# FiberLink_RS232.net
KiCad netlist of a schematic drawn in EAGLE
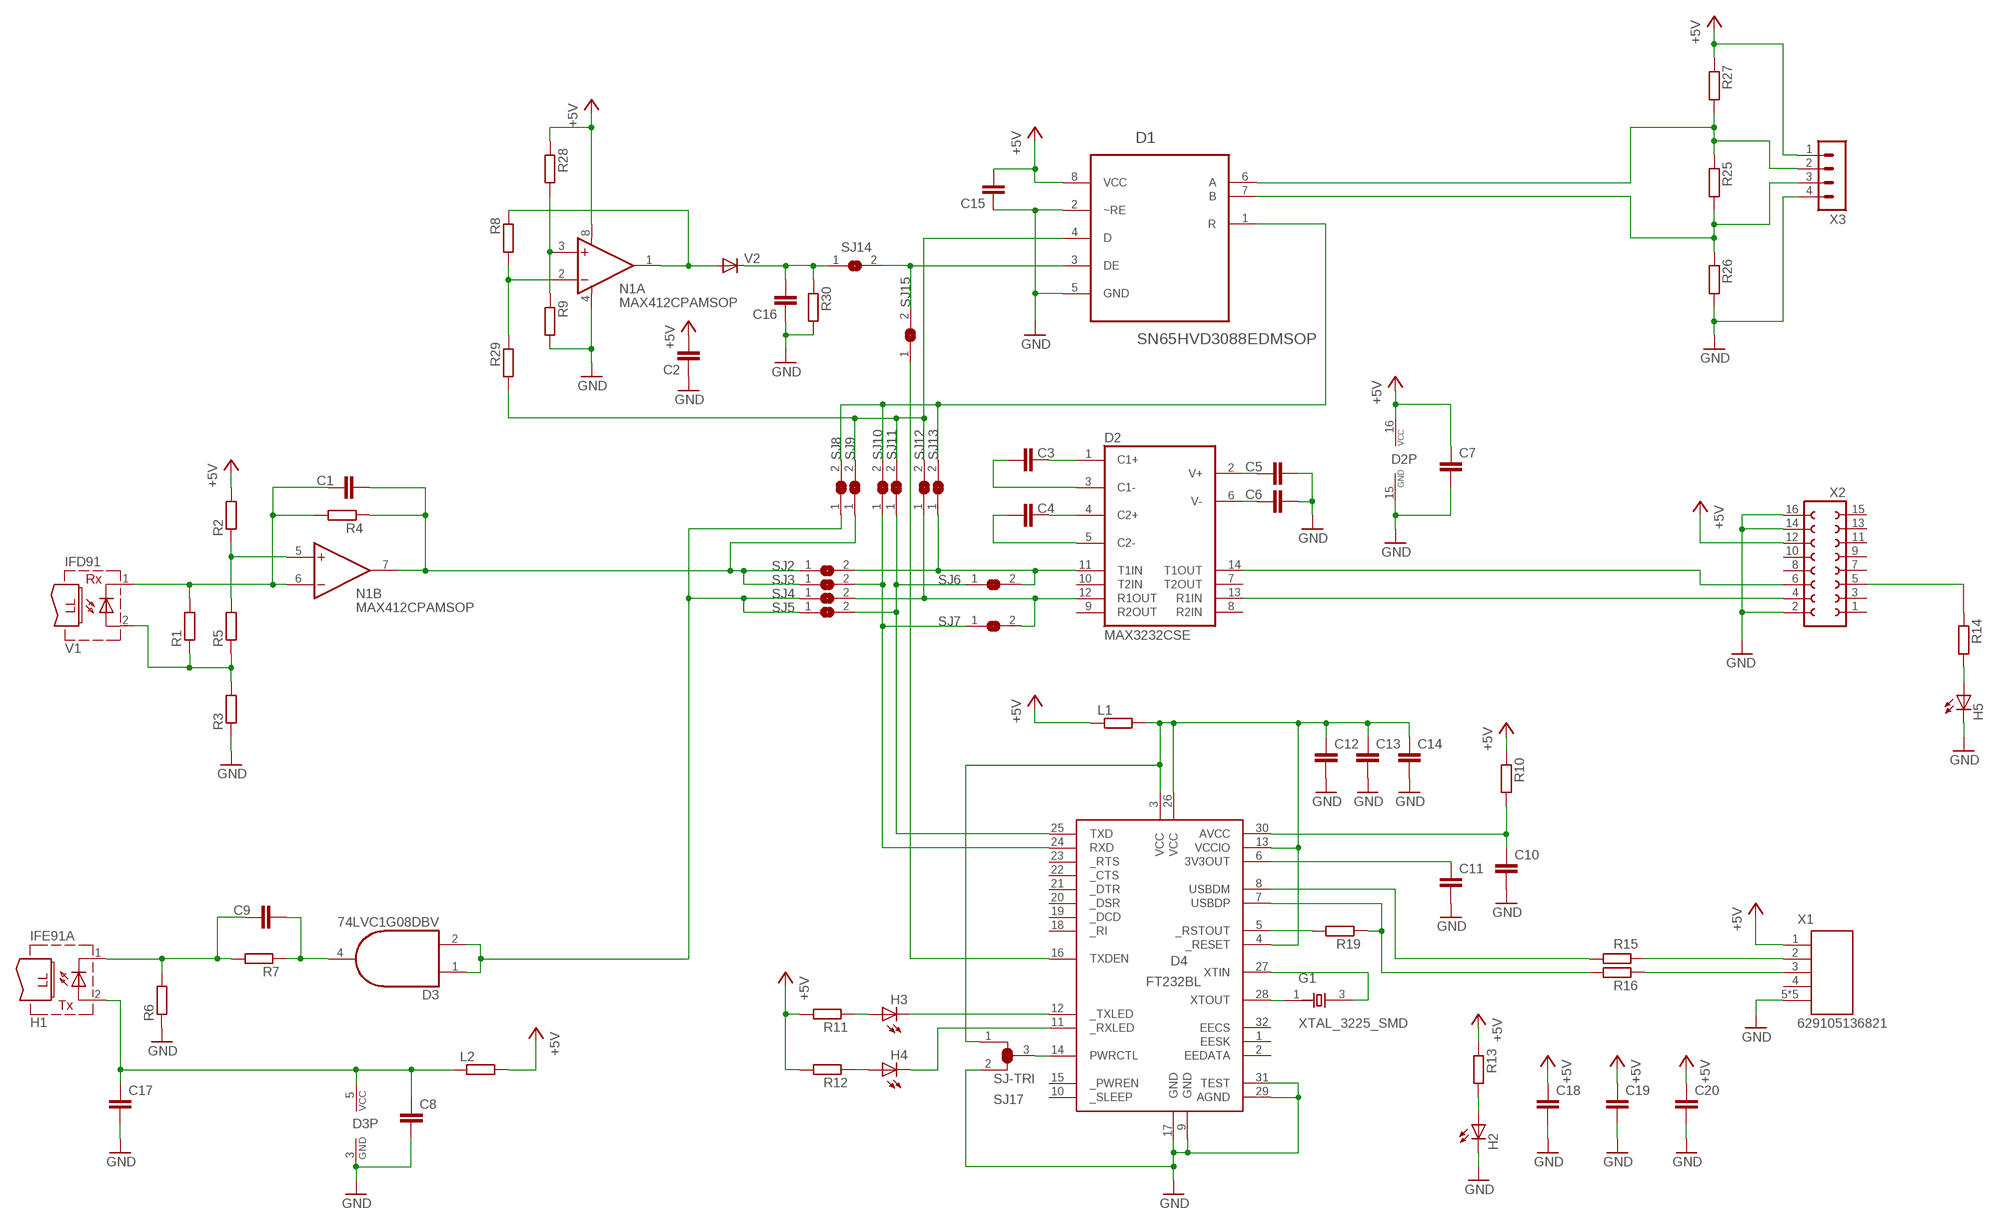
[diagram p0: schematic, sheet 1]

(export (version "E")
  (design (tool "Eeschema 10.0.6"))
  (components
    (comp (ref "C1")
      (value "C-EUC0402")
      (footprint "eagle-import:C0402")
      (libsource (lib "eagle-import") (part "C-EUC0402"))
    )
    (comp (ref "C2")
      (value "C-EUC0402")
      (footprint "eagle-import:C0402")
      (libsource (lib "eagle-import") (part "C-EUC0402"))
    )
    (comp (ref "C3")
      (value "C-EUC0402")
      (footprint "eagle-import:C0402")
      (libsource (lib "eagle-import") (part "C-EUC0402"))
    )
    (comp (ref "C4")
      (value "C-EUC0402")
      (footprint "eagle-import:C0402")
      (libsource (lib "eagle-import") (part "C-EUC0402"))
    )
    (comp (ref "C5")
      (value "C-EUC0402")
      (footprint "eagle-import:C0402")
      (libsource (lib "eagle-import") (part "C-EUC0402"))
    )
    (comp (ref "C6")
      (value "C-EUC0402")
      (footprint "eagle-import:C0402")
      (libsource (lib "eagle-import") (part "C-EUC0402"))
    )
    (comp (ref "C7")
      (value "C-EUC0402")
      (footprint "eagle-import:C0402")
      (libsource (lib "eagle-import") (part "C-EUC0402"))
    )
    (comp (ref "C8")
      (value "C-EUC0402")
      (footprint "eagle-import:C0402")
      (libsource (lib "eagle-import") (part "C-EUC0402"))
    )
    (comp (ref "C9")
      (value "C-EUC0402")
      (footprint "eagle-import:C0402")
      (libsource (lib "eagle-import") (part "C-EUC0402"))
    )
    (comp (ref "C10")
      (value "C-EUC0402")
      (footprint "eagle-import:C0402")
      (libsource (lib "eagle-import") (part "C-EUC0402"))
    )
    (comp (ref "C11")
      (value "C-EUC0402")
      (footprint "eagle-import:C0402")
      (libsource (lib "eagle-import") (part "C-EUC0402"))
    )
    (comp (ref "C12")
      (value "C-EUC0402")
      (footprint "eagle-import:C0402")
      (libsource (lib "eagle-import") (part "C-EUC0402"))
    )
    (comp (ref "C13")
      (value "C-EUC0402")
      (footprint "eagle-import:C0402")
      (libsource (lib "eagle-import") (part "C-EUC0402"))
    )
    (comp (ref "C14")
      (value "C-EUC0402")
      (footprint "eagle-import:C0402")
      (libsource (lib "eagle-import") (part "C-EUC0402"))
    )
    (comp (ref "C15")
      (value "C-EUC0402")
      (footprint "eagle-import:C0402")
      (libsource (lib "eagle-import") (part "C-EUC0402"))
    )
    (comp (ref "C16")
      (value "C-EUC0402")
      (footprint "eagle-import:C0402")
      (libsource (lib "eagle-import") (part "C-EUC0402"))
    )
    (comp (ref "C17")
      (value "C-EUC0402")
      (footprint "eagle-import:C0402")
      (libsource (lib "eagle-import") (part "C-EUC0402"))
    )
    (comp (ref "C18")
      (value "C-EUC0805")
      (footprint "eagle-import:C0805")
      (libsource (lib "eagle-import") (part "C-EUC0805"))
    )
    (comp (ref "C19")
      (value "C-EUC0805")
      (footprint "eagle-import:C0805")
      (libsource (lib "eagle-import") (part "C-EUC0805"))
    )
    (comp (ref "C20")
      (value "C-EUC0805")
      (footprint "eagle-import:C0805")
      (libsource (lib "eagle-import") (part "C-EUC0805"))
    )
    (comp (ref "D1")
      (value "SN65HVD3088EDMSOP")
      (footprint "eagle-import:SOP65P490X110-8N")
      (libsource (lib "eagle-import") (part "SN65HVD3088EDMSOP"))
    )
    (comp (ref "D2")
      (value "MAX3232CSE")
      (footprint "eagle-import:SO16")
      (libsource (lib "eagle-import") (part "MAX3232SEC"))
    )
    (comp (ref "D3")
      (value "74LVC1G08DBV")
      (footprint "eagle-import:SOT23-5")
      (libsource (lib "eagle-import") (part "741G08DBVLVC"))
    )
    (comp (ref "D4")
      (value "FT232BL")
      (footprint "eagle-import:LQFP32")
      (libsource (lib "eagle-import") (part "FT232BL"))
    )
    (comp (ref "G1")
      (value "XTAL_3225_SMD")
      (footprint "eagle-import:X_3225")
      (libsource (lib "eagle-import") (part "XTAL_3225_SMD"))
    )
    (comp (ref "H1")
      (value "IFE91A")
      (footprint "eagle-import:IFO-IFX")
      (libsource (lib "eagle-import") (part "IFE91A"))
    )
    (comp (ref "H2")
      (value "LEDCHIP-LED0603")
      (footprint "eagle-import:CHIP-LED0603")
      (libsource (lib "eagle-import") (part "LEDCHIP-LED0603"))
    )
    (comp (ref "H3")
      (value "LEDCHIP-LED0603")
      (footprint "eagle-import:CHIP-LED0603")
      (libsource (lib "eagle-import") (part "LEDCHIP-LED0603"))
    )
    (comp (ref "H4")
      (value "LEDCHIP-LED0603")
      (footprint "eagle-import:CHIP-LED0603")
      (libsource (lib "eagle-import") (part "LEDCHIP-LED0603"))
    )
    (comp (ref "H5")
      (value "LEDCHIP-LED0603")
      (footprint "eagle-import:CHIP-LED0603")
      (libsource (lib "eagle-import") (part "LEDCHIP-LED0603"))
    )
    (comp (ref "L1")
      (value "R-EU_R0402")
      (footprint "eagle-import:R0402_VISHAY")
      (libsource (lib "eagle-import") (part "R-EU_R0402"))
    )
    (comp (ref "L2")
      (value "R-EU_R0402")
      (footprint "eagle-import:R0402_VISHAY")
      (libsource (lib "eagle-import") (part "R-EU_R0402"))
    )
    (comp (ref "N1")
      (value "MAX412CPAMSOP")
      (footprint "eagle-import:SOP65P490X110-8N")
      (libsource (lib "eagle-import") (part "MAX412CPAMSOP"))
    )
    (comp (ref "R1")
      (value "R-EU_R0402")
      (footprint "eagle-import:R0402_VISHAY")
      (libsource (lib "eagle-import") (part "R-EU_R0402"))
    )
    (comp (ref "R2")
      (value "R-EU_R0402")
      (footprint "eagle-import:R0402_VISHAY")
      (libsource (lib "eagle-import") (part "R-EU_R0402"))
    )
    (comp (ref "R3")
      (value "R-EU_R0402")
      (footprint "eagle-import:R0402_VISHAY")
      (libsource (lib "eagle-import") (part "R-EU_R0402"))
    )
    (comp (ref "R4")
      (value "R-EU_R0402")
      (footprint "eagle-import:R0402_VISHAY")
      (libsource (lib "eagle-import") (part "R-EU_R0402"))
    )
    (comp (ref "R5")
      (value "R-EU_R0402")
      (footprint "eagle-import:R0402_VISHAY")
      (libsource (lib "eagle-import") (part "R-EU_R0402"))
    )
    (comp (ref "R6")
      (value "R-EU_R1206")
      (footprint "eagle-import:R1206")
      (libsource (lib "eagle-import") (part "R-EU_R1206"))
    )
    (comp (ref "R7")
      (value "R-EU_R1206")
      (footprint "eagle-import:R1206")
      (libsource (lib "eagle-import") (part "R-EU_R1206"))
    )
    (comp (ref "R8")
      (value "R-EU_R0402")
      (footprint "eagle-import:R0402_VISHAY")
      (libsource (lib "eagle-import") (part "R-EU_R0402"))
    )
    (comp (ref "R9")
      (value "R-EU_R0402")
      (footprint "eagle-import:R0402_VISHAY")
      (libsource (lib "eagle-import") (part "R-EU_R0402"))
    )
    (comp (ref "R10")
      (value "R-EU_R0402")
      (footprint "eagle-import:R0402_VISHAY")
      (libsource (lib "eagle-import") (part "R-EU_R0402"))
    )
    (comp (ref "R11")
      (value "R-EU_R0402")
      (footprint "eagle-import:R0402_VISHAY")
      (libsource (lib "eagle-import") (part "R-EU_R0402"))
    )
    (comp (ref "R12")
      (value "R-EU_R0402")
      (footprint "eagle-import:R0402_VISHAY")
      (libsource (lib "eagle-import") (part "R-EU_R0402"))
    )
    (comp (ref "R13")
      (value "R-EU_R0402")
      (footprint "eagle-import:R0402_VISHAY")
      (libsource (lib "eagle-import") (part "R-EU_R0402"))
    )
    (comp (ref "R14")
      (value "R-EU_R0402")
      (footprint "eagle-import:R0402_VISHAY")
      (libsource (lib "eagle-import") (part "R-EU_R0402"))
    )
    (comp (ref "R15")
      (value "R-EU_R0402")
      (footprint "eagle-import:R0402_VISHAY")
      (libsource (lib "eagle-import") (part "R-EU_R0402"))
    )
    (comp (ref "R16")
      (value "R-EU_R0402")
      (footprint "eagle-import:R0402_VISHAY")
      (libsource (lib "eagle-import") (part "R-EU_R0402"))
    )
    (comp (ref "R19")
      (value "R-EU_R0402")
      (footprint "eagle-import:R0402_VISHAY")
      (libsource (lib "eagle-import") (part "R-EU_R0402"))
    )
    (comp (ref "R25")
      (value "R-EU_R1206")
      (footprint "eagle-import:R1206")
      (libsource (lib "eagle-import") (part "R-EU_R1206"))
    )
    (comp (ref "R26")
      (value "R-EU_R0603")
      (footprint "eagle-import:R0603")
      (libsource (lib "eagle-import") (part "R-EU_R0603"))
    )
    (comp (ref "R27")
      (value "R-EU_R0603")
      (footprint "eagle-import:R0603")
      (libsource (lib "eagle-import") (part "R-EU_R0603"))
    )
    (comp (ref "R28")
      (value "R-EU_R0402")
      (footprint "eagle-import:R0402_VISHAY")
      (libsource (lib "eagle-import") (part "R-EU_R0402"))
    )
    (comp (ref "R29")
      (value "R-EU_R0402")
      (footprint "eagle-import:R0402_VISHAY")
      (libsource (lib "eagle-import") (part "R-EU_R0402"))
    )
    (comp (ref "R30")
      (value "R-EU_R0402")
      (footprint "eagle-import:R0402_VISHAY")
      (libsource (lib "eagle-import") (part "R-EU_R0402"))
    )
    (comp (ref "SJ2")
      (value "SJ")
      (footprint "eagle-import:SJ-SMALL")
      (libsource (lib "eagle-import") (part "SJ"))
    )
    (comp (ref "SJ3")
      (value "SJ")
      (footprint "eagle-import:SJ-SMALL")
      (libsource (lib "eagle-import") (part "SJ"))
    )
    (comp (ref "SJ4")
      (value "SJ")
      (footprint "eagle-import:SJ-SMALL")
      (libsource (lib "eagle-import") (part "SJ"))
    )
    (comp (ref "SJ5")
      (value "SJ")
      (footprint "eagle-import:SJ-SMALL")
      (libsource (lib "eagle-import") (part "SJ"))
    )
    (comp (ref "SJ6")
      (value "SJ")
      (footprint "eagle-import:SJ-SMALL")
      (libsource (lib "eagle-import") (part "SJ"))
    )
    (comp (ref "SJ7")
      (value "SJ")
      (footprint "eagle-import:SJ-SMALL")
      (libsource (lib "eagle-import") (part "SJ"))
    )
    (comp (ref "SJ8")
      (value "SJ")
      (footprint "eagle-import:SJ-SMALL")
      (libsource (lib "eagle-import") (part "SJ"))
    )
    (comp (ref "SJ9")
      (value "SJ")
      (footprint "eagle-import:SJ-SMALL")
      (libsource (lib "eagle-import") (part "SJ"))
    )
    (comp (ref "SJ10")
      (value "SJ")
      (footprint "eagle-import:SJ-SMALL")
      (libsource (lib "eagle-import") (part "SJ"))
    )
    (comp (ref "SJ11")
      (value "SJ")
      (footprint "eagle-import:SJ-SMALL")
      (libsource (lib "eagle-import") (part "SJ"))
    )
    (comp (ref "SJ12")
      (value "SJ")
      (footprint "eagle-import:SJ-SMALL")
      (libsource (lib "eagle-import") (part "SJ"))
    )
    (comp (ref "SJ13")
      (value "SJ")
      (footprint "eagle-import:SJ-SMALL")
      (libsource (lib "eagle-import") (part "SJ"))
    )
    (comp (ref "SJ14")
      (value "SJ")
      (footprint "eagle-import:SJ-SMALL")
      (libsource (lib "eagle-import") (part "SJ"))
    )
    (comp (ref "SJ15")
      (value "SJ")
      (footprint "eagle-import:SJ-SMALL")
      (libsource (lib "eagle-import") (part "SJ"))
    )
    (comp (ref "SJ17")
      (value "SJ-TRI")
      (footprint "eagle-import:SJ-SMALL-TRI")
      (libsource (lib "eagle-import") (part "SJ-TRI"))
    )
    (comp (ref "V1")
      (value "IFD91")
      (footprint "eagle-import:IFO-IFX")
      (libsource (lib "eagle-import") (part "IFD91"))
    )
    (comp (ref "V2")
      (value "DIODE-SOD323-R")
      (footprint "eagle-import:SOD323-R")
      (libsource (lib "eagle-import") (part "DIODE-SOD323-R"))
    )
    (comp (ref "X1")
      (value "629105136821")
      (footprint "eagle-import:629105136821")
      (libsource (lib "eagle-import") (part "629105136821"))
    )
    (comp (ref "X2")
      (value "FE08-2")
      (footprint "eagle-import:FE08-2")
      (libsource (lib "eagle-import") (part "FE08-2"))
    )
    (comp (ref "X3")
      (value "MA04-1")
      (footprint "eagle-import:MA04-1")
      (libsource (lib "eagle-import") (part "MA04-1"))
    )
  )
  (nets
    (net (code "1") (name "+5V") (class "Default")
      (node (ref "C15") (pin "2") (pinfunction "2_2") (pintype "passive"))
      (node (ref "C18") (pin "1") (pinfunction "1_1") (pintype "passive"))
      (node (ref "C19") (pin "1") (pinfunction "1_1") (pintype "passive"))
      (node (ref "C2") (pin "2") (pinfunction "2_2") (pintype "passive"))
      (node (ref "C20") (pin "1") (pinfunction "1_1") (pintype "passive"))
      (node (ref "C7") (pin "1") (pinfunction "1_1") (pintype "passive"))
      (node (ref "D1") (pin "8") (pinfunction "VCC_8") (pintype "power_in"))
      (node (ref "D2") (pin "16") (pinfunction "VCC_16") (pintype "power_in"))
      (node (ref "L1") (pin "1") (pinfunction "1_1") (pintype "passive"))
      (node (ref "L2") (pin "2") (pinfunction "2_2") (pintype "passive"))
      (node (ref "N1") (pin "8") (pinfunction "V+_8") (pintype "power_in"))
      (node (ref "R10") (pin "1") (pinfunction "1_1") (pintype "passive"))
      (node (ref "R11") (pin "2") (pinfunction "2_2") (pintype "passive"))
      (node (ref "R12") (pin "2") (pinfunction "2_2") (pintype "passive"))
      (node (ref "R13") (pin "1") (pinfunction "1_1") (pintype "passive"))
      (node (ref "R2") (pin "2") (pinfunction "2_2") (pintype "passive"))
      (node (ref "R27") (pin "1") (pinfunction "1_1") (pintype "passive"))
      (node (ref "R28") (pin "1") (pinfunction "1_1") (pintype "passive"))
      (node (ref "X1") (pin "1") (pinfunction "1_1") (pintype "passive"))
      (node (ref "X2") (pin "12") (pinfunction "12_12") (pintype "passive"))
      (node (ref "X3") (pin "1") (pinfunction "1_1") (pintype "passive"))
    )
    (net (code "2") (name "GND") (class "Default")
      (node (ref "C10") (pin "2") (pinfunction "2_2") (pintype "passive"))
      (node (ref "C11") (pin "2") (pinfunction "2_2") (pintype "passive"))
      (node (ref "C12") (pin "2") (pinfunction "2_2") (pintype "passive"))
      (node (ref "C13") (pin "2") (pinfunction "2_2") (pintype "passive"))
      (node (ref "C14") (pin "2") (pinfunction "2_2") (pintype "passive"))
      (node (ref "C15") (pin "1") (pinfunction "1_1") (pintype "passive"))
      (node (ref "C16") (pin "1") (pinfunction "1_1") (pintype "passive"))
      (node (ref "C17") (pin "2") (pinfunction "2_2") (pintype "passive"))
      (node (ref "C18") (pin "2") (pinfunction "2_2") (pintype "passive"))
      (node (ref "C19") (pin "2") (pinfunction "2_2") (pintype "passive"))
      (node (ref "C2") (pin "1") (pinfunction "1_1") (pintype "passive"))
      (node (ref "C20") (pin "2") (pinfunction "2_2") (pintype "passive"))
      (node (ref "C5") (pin "2") (pinfunction "2_2") (pintype "passive"))
      (node (ref "C6") (pin "2") (pinfunction "2_2") (pintype "passive"))
      (node (ref "C7") (pin "2") (pinfunction "2_2") (pintype "passive"))
      (node (ref "C8") (pin "2") (pinfunction "2_2") (pintype "passive"))
      (node (ref "D1") (pin "2") (pinfunction "~{RE}_2") (pintype "input"))
      (node (ref "D1") (pin "5") (pinfunction "GND_5") (pintype "passive"))
      (node (ref "D2") (pin "15") (pinfunction "GND_15") (pintype "power_in"))
      (node (ref "D3") (pin "3") (pinfunction "GND_3") (pintype "power_in"))
      (node (ref "D4") (pin "17") (pinfunction "GND_17") (pintype "power_in"))
      (node (ref "D4") (pin "29") (pinfunction "AGND_29") (pintype "power_in"))
      (node (ref "D4") (pin "31") (pinfunction "TEST_31") (pintype "input"))
      (node (ref "D4") (pin "9") (pinfunction "GND_9") (pintype "power_in"))
      (node (ref "H2") (pin "C") (pinfunction "C_C") (pintype "passive"))
      (node (ref "H5") (pin "C") (pinfunction "C_C") (pintype "passive"))
      (node (ref "N1") (pin "4") (pinfunction "V-_4") (pintype "power_in"))
      (node (ref "R26") (pin "2") (pinfunction "2_2") (pintype "passive"))
      (node (ref "R3") (pin "1") (pinfunction "1_1") (pintype "passive"))
      (node (ref "R30") (pin "2") (pinfunction "2_2") (pintype "passive"))
      (node (ref "R6") (pin "1") (pinfunction "1_1") (pintype "passive"))
      (node (ref "R9") (pin "2") (pinfunction "2_2") (pintype "passive"))
      (node (ref "SJ17") (pin "2") (pinfunction "2_2") (pintype "passive"))
      (node (ref "X1") (pin "5") (pinfunction "5_5") (pintype "passive"))
      (node (ref "X1") (pin "Z1") (pinfunction "5_Z1") (pintype "passive"))
      (node (ref "X1") (pin "Z2") (pinfunction "5_Z2") (pintype "passive"))
      (node (ref "X1") (pin "Z3") (pinfunction "5_Z3") (pintype "passive"))
      (node (ref "X1") (pin "Z4") (pinfunction "5_Z4") (pintype "passive"))
      (node (ref "X2") (pin "14") (pinfunction "14_14") (pintype "passive"))
      (node (ref "X2") (pin "16") (pinfunction "16_16") (pintype "passive"))
      (node (ref "X2") (pin "2") (pinfunction "2_2") (pintype "passive"))
      (node (ref "X3") (pin "4") (pinfunction "4_4") (pintype "passive"))
    )
    (net (code "3") (name "Net-(C16-Pad2)") (class "Default")
      (node (ref "C16") (pin "2") (pinfunction "2_2") (pintype "passive"))
      (node (ref "R30") (pin "1") (pinfunction "1_1") (pintype "passive"))
      (node (ref "SJ14") (pin "1") (pinfunction "1_1") (pintype "passive"))
      (node (ref "V2") (pin "C") (pinfunction "C_C") (pintype "passive"))
    )
    (net (code "4") (name "Net-(D1-A)") (class "Default")
      (node (ref "D1") (pin "6") (pinfunction "A_6") (pintype "output"))
      (node (ref "R25") (pin "1") (pinfunction "1_1") (pintype "passive"))
      (node (ref "R27") (pin "2") (pinfunction "2_2") (pintype "passive"))
      (node (ref "X3") (pin "2") (pinfunction "2_2") (pintype "passive"))
    )
    (net (code "5") (name "Net-(D1-B)") (class "Default")
      (node (ref "D1") (pin "7") (pinfunction "B_7") (pintype "output"))
      (node (ref "R25") (pin "2") (pinfunction "2_2") (pintype "passive"))
      (node (ref "R26") (pin "1") (pinfunction "1_1") (pintype "passive"))
      (node (ref "X3") (pin "3") (pinfunction "3_3") (pintype "passive"))
    )
    (net (code "6") (name "Net-(D1-D)") (class "Default")
      (node (ref "D1") (pin "4") (pinfunction "D_4") (pintype "input"))
      (node (ref "R29") (pin "2") (pinfunction "2_2") (pintype "passive"))
      (node (ref "SJ11") (pin "2") (pinfunction "2_2") (pintype "passive"))
      (node (ref "SJ12") (pin "2") (pinfunction "2_2") (pintype "passive"))
      (node (ref "SJ9") (pin "2") (pinfunction "2_2") (pintype "passive"))
    )
    (net (code "7") (name "Net-(D1-DE)") (class "Default")
      (node (ref "D1") (pin "3") (pinfunction "DE_3") (pintype "input"))
      (node (ref "SJ14") (pin "2") (pinfunction "2_2") (pintype "passive"))
      (node (ref "SJ15") (pin "2") (pinfunction "2_2") (pintype "passive"))
    )
    (net (code "8") (name "Net-(D1-R)") (class "Default")
      (node (ref "D1") (pin "1") (pinfunction "R_1") (pintype "output"))
      (node (ref "SJ10") (pin "2") (pinfunction "2_2") (pintype "passive"))
      (node (ref "SJ13") (pin "2") (pinfunction "2_2") (pintype "passive"))
      (node (ref "SJ8") (pin "2") (pinfunction "2_2") (pintype "passive"))
    )
    (net (code "9") (name "Net-(D2A-C1+)") (class "Default")
      (node (ref "C3") (pin "1") (pinfunction "1_1") (pintype "passive"))
      (node (ref "D2") (pin "1") (pinfunction "C1+_1") (pintype "bidirectional"))
    )
    (net (code "10") (name "Net-(D2A-C1-)") (class "Default")
      (node (ref "C3") (pin "2") (pinfunction "2_2") (pintype "passive"))
      (node (ref "D2") (pin "3") (pinfunction "C1-_3") (pintype "bidirectional"))
    )
    (net (code "11") (name "Net-(D2A-C2+)") (class "Default")
      (node (ref "C4") (pin "1") (pinfunction "1_1") (pintype "passive"))
      (node (ref "D2") (pin "4") (pinfunction "C2+_4") (pintype "bidirectional"))
    )
    (net (code "12") (name "Net-(D2A-C2-)") (class "Default")
      (node (ref "C4") (pin "2") (pinfunction "2_2") (pintype "passive"))
      (node (ref "D2") (pin "5") (pinfunction "C2-_5") (pintype "bidirectional"))
    )
    (net (code "13") (name "Net-(D2A-R1IN)") (class "Default")
      (node (ref "D2") (pin "13") (pinfunction "R1IN_13") (pintype "input"))
      (node (ref "X2") (pin "4") (pinfunction "4_4") (pintype "passive"))
    )
    (net (code "14") (name "Net-(D2A-R1OUT)") (class "Default")
      (node (ref "D2") (pin "12") (pinfunction "R1OUT_12") (pintype "output"))
      (node (ref "SJ12") (pin "1") (pinfunction "1_1") (pintype "passive"))
      (node (ref "SJ4") (pin "2") (pinfunction "2_2") (pintype "passive"))
      (node (ref "SJ7") (pin "2") (pinfunction "2_2") (pintype "passive"))
    )
    (net (code "15") (name "Net-(D2A-T1IN)") (class "Default")
      (node (ref "D2") (pin "11") (pinfunction "T1IN_11") (pintype "input"))
      (node (ref "SJ13") (pin "1") (pinfunction "1_1") (pintype "passive"))
      (node (ref "SJ2") (pin "2") (pinfunction "2_2") (pintype "passive"))
      (node (ref "SJ6") (pin "2") (pinfunction "2_2") (pintype "passive"))
    )
    (net (code "16") (name "Net-(D2A-T1OUT)") (class "Default")
      (node (ref "D2") (pin "14") (pinfunction "T1OUT_14") (pintype "output"))
      (node (ref "X2") (pin "6") (pinfunction "6_6") (pintype "passive"))
    )
    (net (code "17") (name "Net-(D2A-V+)") (class "Default")
      (node (ref "C5") (pin "1") (pinfunction "1_1") (pintype "passive"))
      (node (ref "D2") (pin "2") (pinfunction "V+_2") (pintype "bidirectional"))
    )
    (net (code "18") (name "Net-(D2A-V-)") (class "Default")
      (node (ref "C6") (pin "1") (pinfunction "1_1") (pintype "passive"))
      (node (ref "D2") (pin "6") (pinfunction "V-_6") (pintype "bidirectional"))
    )
    (net (code "19") (name "Net-(D3A-I0)") (class "Default")
      (node (ref "D3") (pin "1") (pinfunction "I0_1") (pintype "input"))
      (node (ref "D3") (pin "2") (pinfunction "I1_2") (pintype "input"))
      (node (ref "SJ4") (pin "1") (pinfunction "1_1") (pintype "passive"))
      (node (ref "SJ5") (pin "1") (pinfunction "1_1") (pintype "passive"))
      (node (ref "SJ8") (pin "1") (pinfunction "1_1") (pintype "passive"))
    )
    (net (code "20") (name "Net-(D3A-O)") (class "Default")
      (node (ref "C9") (pin "2") (pinfunction "2_2") (pintype "passive"))
      (node (ref "D3") (pin "4") (pinfunction "O_4") (pintype "output"))
      (node (ref "R7") (pin "1") (pinfunction "1_1") (pintype "passive"))
    )
    (net (code "21") (name "Net-(D3B-VCC)") (class "Default")
      (node (ref "C17") (pin "1") (pinfunction "1_1") (pintype "passive"))
      (node (ref "C8") (pin "1") (pinfunction "1_1") (pintype "passive"))
      (node (ref "D3") (pin "5") (pinfunction "VCC_5") (pintype "power_in"))
      (node (ref "H1") (pin "2") (pinfunction "A_2") (pintype "passive"))
      (node (ref "L2") (pin "1") (pinfunction "1_1") (pintype "passive"))
    )
    (net (code "22") (name "Net-(D4-3V3OUT)") (class "Default")
      (node (ref "C11") (pin "1") (pinfunction "1_1") (pintype "passive"))
      (node (ref "D4") (pin "6") (pinfunction "3V3OUT_6") (pintype "output"))
    )
    (net (code "23") (name "Net-(D4-AVCC)") (class "Default")
      (node (ref "C10") (pin "1") (pinfunction "1_1") (pintype "passive"))
      (node (ref "D4") (pin "30") (pinfunction "AVCC_30") (pintype "power_in"))
      (node (ref "R10") (pin "2") (pinfunction "2_2") (pintype "passive"))
    )
    (net (code "24") (name "Net-(D4-PWRCTL)") (class "Default")
      (node (ref "D4") (pin "14") (pinfunction "PWRCTL_14") (pintype "input"))
      (node (ref "SJ17") (pin "3") (pinfunction "3_3") (pintype "passive"))
    )
    (net (code "25") (name "Net-(D4-RXD)") (class "Default")
      (node (ref "D4") (pin "24") (pinfunction "RXD_24") (pintype "input"))
      (node (ref "SJ10") (pin "1") (pinfunction "1_1") (pintype "passive"))
      (node (ref "SJ3") (pin "2") (pinfunction "2_2") (pintype "passive"))
      (node (ref "SJ7") (pin "1") (pinfunction "1_1") (pintype "passive"))
    )
    (net (code "26") (name "Net-(D4-TXD)") (class "Default")
      (node (ref "D4") (pin "25") (pinfunction "TXD_25") (pintype "output"))
      (node (ref "SJ11") (pin "1") (pinfunction "1_1") (pintype "passive"))
      (node (ref "SJ5") (pin "2") (pinfunction "2_2") (pintype "passive"))
      (node (ref "SJ6") (pin "1") (pinfunction "1_1") (pintype "passive"))
    )
    (net (code "27") (name "Net-(D4-TXDEN)") (class "Default")
      (node (ref "D4") (pin "16") (pinfunction "TXDEN_16") (pintype "output"))
      (node (ref "SJ15") (pin "1") (pinfunction "1_1") (pintype "passive"))
    )
    (net (code "28") (name "Net-(D4-USBDM)") (class "Default")
      (node (ref "D4") (pin "8") (pinfunction "USBDM_8") (pintype "bidirectional"))
      (node (ref "R15") (pin "2") (pinfunction "2_2") (pintype "passive"))
    )
    (net (code "29") (name "Net-(D4-USBDP)") (class "Default")
      (node (ref "D4") (pin "7") (pinfunction "USBDP_7") (pintype "bidirectional"))
      (node (ref "R16") (pin "2") (pinfunction "2_2") (pintype "passive"))
      (node (ref "R19") (pin "1") (pinfunction "1_1") (pintype "passive"))
    )
    (net (code "30") (name "Net-(D4-VCCIO)") (class "Default")
      (node (ref "C12") (pin "1") (pinfunction "1_1") (pintype "passive"))
      (node (ref "C13") (pin "1") (pinfunction "1_1") (pintype "passive"))
      (node (ref "C14") (pin "1") (pinfunction "1_1") (pintype "passive"))
      (node (ref "D4") (pin "13") (pinfunction "VCCIO_13") (pintype "power_in"))
      (node (ref "D4") (pin "26") (pinfunction "VCC_26") (pintype "power_in"))
      (node (ref "D4") (pin "3") (pinfunction "VCC_3") (pintype "power_in"))
      (node (ref "D4") (pin "4") (pinfunction "_RESET_4") (pintype "input"))
      (node (ref "L1") (pin "2") (pinfunction "2_2") (pintype "passive"))
      (node (ref "SJ17") (pin "1") (pinfunction "1_1") (pintype "passive"))
    )
    (net (code "31") (name "Net-(D4-XTIN)") (class "Default")
      (node (ref "D4") (pin "27") (pinfunction "XTIN_27") (pintype "input"))
      (node (ref "G1") (pin "3") (pinfunction "X2_3") (pintype "bidirectional"))
    )
    (net (code "32") (name "Net-(D4-XTOUT)") (class "Default")
      (node (ref "D4") (pin "28") (pinfunction "XTOUT_28") (pintype "output"))
      (node (ref "G1") (pin "1") (pinfunction "X1_1") (pintype "bidirectional"))
    )
    (net (code "33") (name "Net-(D4-_RSTOUT)") (class "Default")
      (node (ref "D4") (pin "5") (pinfunction "_RSTOUT_5") (pintype "output"))
      (node (ref "R19") (pin "2") (pinfunction "2_2") (pintype "passive"))
    )
    (net (code "34") (name "Net-(D4-_RXLED)") (class "Default")
      (node (ref "D4") (pin "11") (pinfunction "_RXLED_11") (pintype "open_collector"))
      (node (ref "H4") (pin "C") (pinfunction "C_C") (pintype "passive"))
    )
    (net (code "35") (name "Net-(D4-_TXLED)") (class "Default")
      (node (ref "D4") (pin "12") (pinfunction "_TXLED_12") (pintype "open_collector"))
      (node (ref "H3") (pin "C") (pinfunction "C_C") (pintype "passive"))
    )
    (net (code "36") (name "Net-(H1-C)") (class "Default")
      (node (ref "C9") (pin "1") (pinfunction "1_1") (pintype "passive"))
      (node (ref "H1") (pin "1") (pinfunction "C_1") (pintype "passive"))
      (node (ref "R6") (pin "2") (pinfunction "2_2") (pintype "passive"))
      (node (ref "R7") (pin "2") (pinfunction "2_2") (pintype "passive"))
    )
    (net (code "37") (name "Net-(H2-PadA)") (class "Default")
      (node (ref "H2") (pin "A") (pinfunction "A_A") (pintype "passive"))
      (node (ref "R13") (pin "2") (pinfunction "2_2") (pintype "passive"))
    )
    (net (code "38") (name "Net-(H3-PadA)") (class "Default")
      (node (ref "H3") (pin "A") (pinfunction "A_A") (pintype "passive"))
      (node (ref "R11") (pin "1") (pinfunction "1_1") (pintype "passive"))
    )
    (net (code "39") (name "Net-(H4-PadA)") (class "Default")
      (node (ref "H4") (pin "A") (pinfunction "A_A") (pintype "passive"))
      (node (ref "R12") (pin "1") (pinfunction "1_1") (pintype "passive"))
    )
    (net (code "40") (name "Net-(H5-PadA)") (class "Default")
      (node (ref "H5") (pin "A") (pinfunction "A_A") (pintype "passive"))
      (node (ref "R14") (pin "2") (pinfunction "2_2") (pintype "passive"))
    )
    (net (code "41") (name "Net-(N1A-+IN)") (class "Default")
      (node (ref "N1") (pin "3") (pinfunction "+IN_3") (pintype "input"))
      (node (ref "R28") (pin "2") (pinfunction "2_2") (pintype "passive"))
      (node (ref "R9") (pin "1") (pinfunction "1_1") (pintype "passive"))
    )
    (net (code "42") (name "Net-(N1A--IN)") (class "Default")
      (node (ref "N1") (pin "2") (pinfunction "-IN_2") (pintype "input"))
      (node (ref "R29") (pin "1") (pinfunction "1_1") (pintype "passive"))
      (node (ref "R8") (pin "2") (pinfunction "2_2") (pintype "passive"))
    )
    (net (code "43") (name "Net-(N1A-OUT)") (class "Default")
      (node (ref "N1") (pin "1") (pinfunction "OUT_1") (pintype "output"))
      (node (ref "R8") (pin "1") (pinfunction "1_1") (pintype "passive"))
      (node (ref "V2") (pin "A") (pinfunction "A_A") (pintype "passive"))
    )
    (net (code "44") (name "Net-(N1B-+IN)") (class "Default")
      (node (ref "N1") (pin "5") (pinfunction "+IN_5") (pintype "input"))
      (node (ref "R2") (pin "1") (pinfunction "1_1") (pintype "passive"))
      (node (ref "R5") (pin "2") (pinfunction "2_2") (pintype "passive"))
    )
    (net (code "45") (name "Net-(N1B--IN)") (class "Default")
      (node (ref "C1") (pin "1") (pinfunction "1_1") (pintype "passive"))
      (node (ref "N1") (pin "6") (pinfunction "-IN_6") (pintype "input"))
      (node (ref "R1") (pin "2") (pinfunction "2_2") (pintype "passive"))
      (node (ref "R4") (pin "2") (pinfunction "2_2") (pintype "passive"))
      (node (ref "V1") (pin "1") (pinfunction "C_1") (pintype "passive"))
    )
    (net (code "46") (name "Net-(N1B-OUT)") (class "Default")
      (node (ref "C1") (pin "2") (pinfunction "2_2") (pintype "passive"))
      (node (ref "N1") (pin "7") (pinfunction "OUT_7") (pintype "output"))
      (node (ref "R4") (pin "1") (pinfunction "1_1") (pintype "passive"))
      (node (ref "SJ2") (pin "1") (pinfunction "1_1") (pintype "passive"))
      (node (ref "SJ3") (pin "1") (pinfunction "1_1") (pintype "passive"))
      (node (ref "SJ9") (pin "1") (pinfunction "1_1") (pintype "passive"))
    )
    (net (code "47") (name "Net-(R14-Pad1)") (class "Default")
      (node (ref "R14") (pin "1") (pinfunction "1_1") (pintype "passive"))
      (node (ref "X2") (pin "5") (pinfunction "5_5") (pintype "passive"))
    )
    (net (code "48") (name "Net-(R15-Pad1)") (class "Default")
      (node (ref "R15") (pin "1") (pinfunction "1_1") (pintype "passive"))
      (node (ref "X1") (pin "2") (pinfunction "2_2") (pintype "passive"))
    )
    (net (code "49") (name "Net-(R16-Pad1)") (class "Default")
      (node (ref "R16") (pin "1") (pinfunction "1_1") (pintype "passive"))
      (node (ref "X1") (pin "3") (pinfunction "3_3") (pintype "passive"))
    )
    (net (code "50") (name "Net-(V1-A)") (class "Default")
      (node (ref "R1") (pin "1") (pinfunction "1_1") (pintype "passive"))
      (node (ref "R3") (pin "2") (pinfunction "2_2") (pintype "passive"))
      (node (ref "R5") (pin "1") (pinfunction "1_1") (pintype "passive"))
      (node (ref "V1") (pin "2") (pinfunction "A_2") (pintype "passive"))
    )
    (net (code "51") (name "unconnected-(D2A-R2IN-Pad8)") (class "Default")
      (node (ref "D2") (pin "8") (pinfunction "R2IN_8") (pintype "input"))
    )
    (net (code "52") (name "unconnected-(D2A-R2OUT-Pad9)") (class "Default")
      (node (ref "D2") (pin "9") (pinfunction "R2OUT_9") (pintype "output"))
    )
    (net (code "53") (name "unconnected-(D2A-T2IN-Pad10)") (class "Default")
      (node (ref "D2") (pin "10") (pinfunction "T2IN_10") (pintype "input"))
    )
    (net (code "54") (name "unconnected-(D2A-T2OUT-Pad7)") (class "Default")
      (node (ref "D2") (pin "7") (pinfunction "T2OUT_7") (pintype "output"))
    )
    (net (code "55") (name "unconnected-(D4-EECS-Pad32)") (class "Default")
      (node (ref "D4") (pin "32") (pinfunction "EECS_32") (pintype "bidirectional"))
    )
    (net (code "56") (name "unconnected-(D4-EEDATA-Pad2)") (class "Default")
      (node (ref "D4") (pin "2") (pinfunction "EEDATA_2") (pintype "bidirectional"))
    )
    (net (code "57") (name "unconnected-(D4-EESK-Pad1)") (class "Default")
      (node (ref "D4") (pin "1") (pinfunction "EESK_1") (pintype "output"))
    )
    (net (code "58") (name "unconnected-(D4-_CTS-Pad22)") (class "Default")
      (node (ref "D4") (pin "22") (pinfunction "_CTS_22") (pintype "input"))
    )
    (net (code "59") (name "unconnected-(D4-_DCD-Pad19)") (class "Default")
      (node (ref "D4") (pin "19") (pinfunction "_DCD_19") (pintype "input"))
    )
    (net (code "60") (name "unconnected-(D4-_DSR-Pad20)") (class "Default")
      (node (ref "D4") (pin "20") (pinfunction "_DSR_20") (pintype "input"))
    )
    (net (code "61") (name "unconnected-(D4-_DTR-Pad21)") (class "Default")
      (node (ref "D4") (pin "21") (pinfunction "_DTR_21") (pintype "output"))
    )
    (net (code "62") (name "unconnected-(D4-_PWREN-Pad15)") (class "Default")
      (node (ref "D4") (pin "15") (pinfunction "_PWREN_15") (pintype "output"))
    )
    (net (code "63") (name "unconnected-(D4-_RI-Pad18)") (class "Default")
      (node (ref "D4") (pin "18") (pinfunction "_RI_18") (pintype "input"))
    )
    (net (code "64") (name "unconnected-(D4-_RTS-Pad23)") (class "Default")
      (node (ref "D4") (pin "23") (pinfunction "_RTS_23") (pintype "output"))
    )
    (net (code "65") (name "unconnected-(D4-_SLEEP-Pad10)") (class "Default")
      (node (ref "D4") (pin "10") (pinfunction "_SLEEP_10") (pintype "output"))
    )
    (net (code "66") (name "unconnected-(X1-Pad4)") (class "Default")
      (node (ref "X1") (pin "4") (pinfunction "4_4") (pintype "passive"))
    )
    (net (code "67") (name "unconnected-(X2-Pad1)") (class "Default")
      (node (ref "X2") (pin "1") (pinfunction "1_1") (pintype "passive"))
    )
    (net (code "68") (name "unconnected-(X2-Pad3)") (class "Default")
      (node (ref "X2") (pin "3") (pinfunction "3_3") (pintype "passive"))
    )
    (net (code "69") (name "unconnected-(X2-Pad7)") (class "Default")
      (node (ref "X2") (pin "7") (pinfunction "7_7") (pintype "passive"))
    )
    (net (code "70") (name "unconnected-(X2-Pad8)") (class "Default")
      (node (ref "X2") (pin "8") (pinfunction "8_8") (pintype "passive"))
    )
    (net (code "71") (name "unconnected-(X2-Pad9)") (class "Default")
      (node (ref "X2") (pin "9") (pinfunction "9_9") (pintype "passive"))
    )
    (net (code "72") (name "unconnected-(X2-Pad10)") (class "Default")
      (node (ref "X2") (pin "10") (pinfunction "10_10") (pintype "passive"))
    )
    (net (code "73") (name "unconnected-(X2-Pad11)") (class "Default")
      (node (ref "X2") (pin "11") (pinfunction "11_11") (pintype "passive"))
    )
    (net (code "74") (name "unconnected-(X2-Pad13)") (class "Default")
      (node (ref "X2") (pin "13") (pinfunction "13_13") (pintype "passive"))
    )
    (net (code "75") (name "unconnected-(X2-Pad15)") (class "Default")
      (node (ref "X2") (pin "15") (pinfunction "15_15") (pintype "passive"))
    )
  )
)
